# Electronic_Schematic.net
KiCad netlist of a schematic drawn in EAGLE
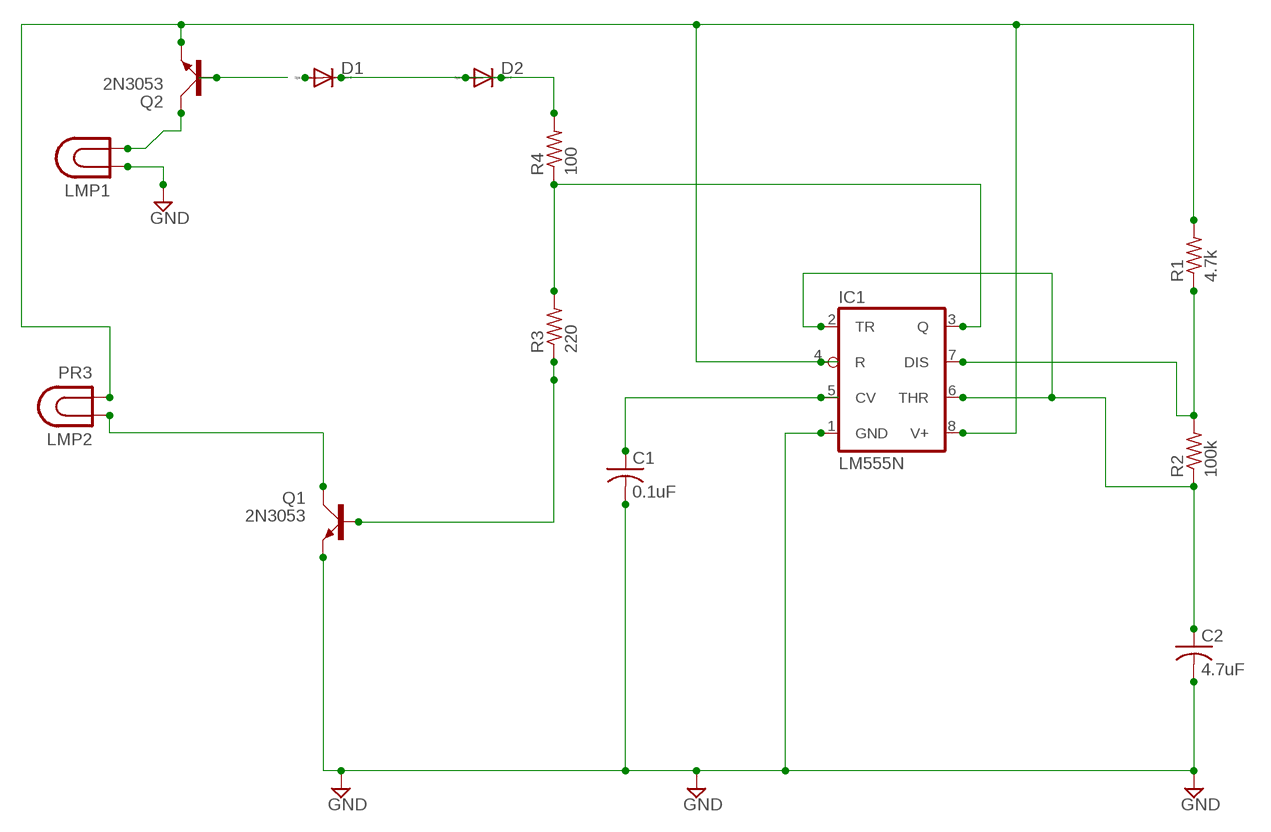
[diagram p0: schematic, sheet 1]

(export (version "E")
  (design (tool "Eeschema 10.0.6"))
  (components
    (comp (ref "C1")
      (value "0.1uF")
      (footprint "eagle-import:C050-025X075")
      (libsource (lib "eagle-import") (part "C-US050-025X075"))
    )
    (comp (ref "C2")
      (value "4.7uF")
      (footprint "eagle-import:C025_050-025X075")
      (libsource (lib "eagle-import") (part "C-US025_050-025X075"))
    )
    (comp (ref "D1")
      (value "DIODE-D-2.5")
      (footprint "eagle-import:D-2.5")
      (libsource (lib "eagle-import") (part "DIODE-D-2.5"))
    )
    (comp (ref "D2")
      (value "DIODE-D-2.5")
      (footprint "eagle-import:D-2.5")
      (libsource (lib "eagle-import") (part "DIODE-D-2.5"))
    )
    (comp (ref "IC1")
      (value "LM555N")
      (footprint "eagle-import:DIL08")
      (libsource (lib "eagle-import") (part "555NLM"))
    )
    (comp (ref "LMP1")
      (value "LAMP")
      (footprint "eagle-import:LDH-5R")
      (libsource (lib "eagle-import") (part "LAMP"))
    )
    (comp (ref "LMP2")
      (value "PR3")
      (footprint "eagle-import:LDH-5R")
      (libsource (lib "eagle-import") (part "LAMP"))
    )
    (comp (ref "Q1")
      (value "2N3053")
      (footprint "eagle-import:TO39")
      (libsource (lib "eagle-import") (part "2N3053"))
    )
    (comp (ref "Q2")
      (value "2N3053")
      (footprint "eagle-import:TO39")
      (libsource (lib "eagle-import") (part "2N3053"))
    )
    (comp (ref "R1")
      (value "4.7k")
      (footprint "eagle-import:0207_2V")
      (libsource (lib "eagle-import") (part "R-US_0207/2V"))
    )
    (comp (ref "R2")
      (value "100k")
      (footprint "eagle-import:0207_2V")
      (libsource (lib "eagle-import") (part "R-US_0207/2V"))
    )
    (comp (ref "R3")
      (value "220")
      (footprint "eagle-import:0207_2V")
      (libsource (lib "eagle-import") (part "R-US_0207/2V"))
    )
    (comp (ref "R4")
      (value "100")
      (footprint "eagle-import:0207_2V")
      (libsource (lib "eagle-import") (part "R-US_0207/2V"))
    )
  )
  (nets
    (net (code "1") (name "GND") (class "Default")
      (node (ref "C1") (pin "2") (pinfunction "2_2") (pintype "passive"))
      (node (ref "C2") (pin "2") (pinfunction "2_2") (pintype "passive"))
      (node (ref "IC1") (pin "1") (pinfunction "GND_1") (pintype "power_in"))
      (node (ref "LMP1") (pin "1") (pinfunction "1_1") (pintype "passive"))
      (node (ref "Q1") (pin "1") (pinfunction "E_1") (pintype "passive"))
    )
    (net (code "2") (name "Net-(D1-PadC)") (class "Default")
      (node (ref "D1") (pin "C") (pinfunction "C_C") (pintype "passive"))
      (node (ref "D2") (pin "A") (pinfunction "A_A") (pintype "passive"))
      (node (ref "D2") (pin "C") (pinfunction "C_C") (pintype "passive"))
      (node (ref "R4") (pin "2") (pinfunction "2_2") (pintype "passive"))
    )
    (net (code "3") (name "Net-(IC1-CV)") (class "Default")
      (node (ref "C1") (pin "1") (pinfunction "1_1") (pintype "passive"))
      (node (ref "IC1") (pin "5") (pinfunction "CV_5") (pintype "input"))
    )
    (net (code "4") (name "Net-(IC1-DIS)") (class "Default")
      (node (ref "IC1") (pin "7") (pinfunction "DIS_7") (pintype "input"))
      (node (ref "R1") (pin "1") (pinfunction "1_1") (pintype "passive"))
      (node (ref "R2") (pin "2") (pinfunction "2_2") (pintype "passive"))
    )
    (net (code "5") (name "Net-(IC1-Q)") (class "Default")
      (node (ref "IC1") (pin "3") (pinfunction "Q_3") (pintype "output"))
      (node (ref "R3") (pin "2") (pinfunction "2_2") (pintype "passive"))
      (node (ref "R4") (pin "1") (pinfunction "1_1") (pintype "passive"))
    )
    (net (code "6") (name "Net-(IC1-R)") (class "Default")
      (node (ref "IC1") (pin "4") (pinfunction "R_4") (pintype "input"))
      (node (ref "IC1") (pin "8") (pinfunction "V+_8") (pintype "power_in"))
      (node (ref "LMP2") (pin "2") (pinfunction "2_2") (pintype "passive"))
      (node (ref "Q2") (pin "1") (pinfunction "E_1") (pintype "passive"))
      (node (ref "R1") (pin "2") (pinfunction "2_2") (pintype "passive"))
    )
    (net (code "7") (name "Net-(IC1-THR)") (class "Default")
      (node (ref "C2") (pin "1") (pinfunction "1_1") (pintype "passive"))
      (node (ref "IC1") (pin "2") (pinfunction "TR_2") (pintype "input"))
      (node (ref "IC1") (pin "6") (pinfunction "THR_6") (pintype "input"))
      (node (ref "R2") (pin "1") (pinfunction "1_1") (pintype "passive"))
    )
    (net (code "8") (name "Net-(Q1-B)") (class "Default")
      (node (ref "Q1") (pin "2") (pinfunction "B_2") (pintype "passive"))
      (node (ref "R3") (pin "1") (pinfunction "1_1") (pintype "passive"))
    )
    (net (code "9") (name "Net-(Q1-C)") (class "Default")
      (node (ref "LMP2") (pin "1") (pinfunction "1_1") (pintype "passive"))
      (node (ref "Q1") (pin "3") (pinfunction "C_3") (pintype "passive"))
    )
    (net (code "10") (name "Net-(Q2-C)") (class "Default")
      (node (ref "LMP1") (pin "2") (pinfunction "2_2") (pintype "passive"))
      (node (ref "Q2") (pin "3") (pinfunction "C_3") (pintype "passive"))
    )
    (net (code "11") (name "unconnected-(D1-PadA)") (class "Default")
      (node (ref "D1") (pin "A") (pinfunction "A_A") (pintype "passive"))
    )
    (net (code "12") (name "unconnected-(Q2-B-Pad2)") (class "Default")
      (node (ref "Q2") (pin "2") (pinfunction "B_2") (pintype "passive"))
    )
  )
)
